# working.net
KiCad netlist of a schematic drawn in EAGLE
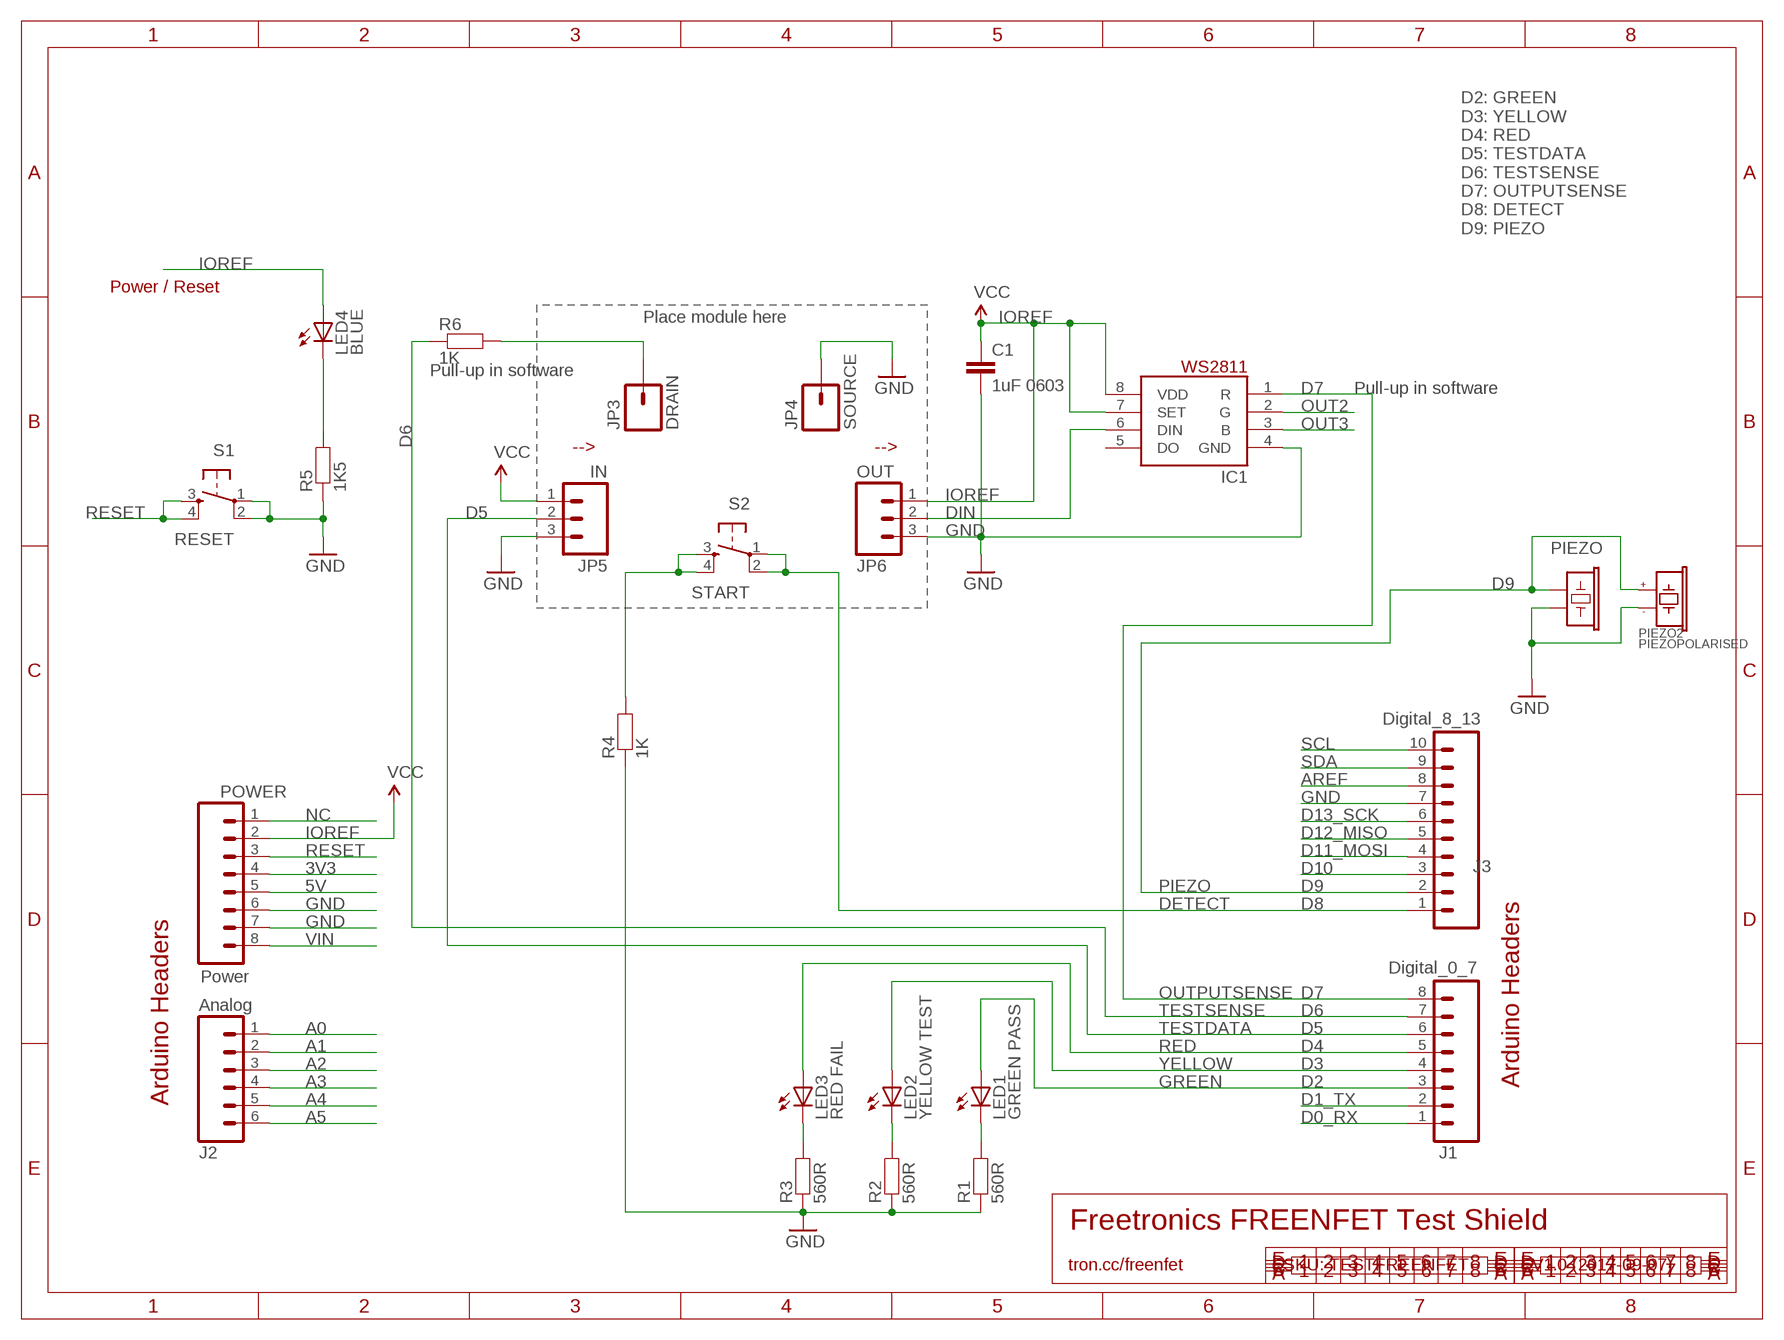
[diagram p0: schematic, sheet 1]

(export (version "E")
  (design (tool "Eeschema 10.0.6"))
  (components
    (comp (ref "C1")
      (value "1uF 0603")
      (footprint "eagle-import:0603")
      (libsource (lib "eagle-import") (part "CAP0603"))
    )
    (comp (ref "IC1")
      (value "WS2811-SOP8")
      (footprint "eagle-import:SO08-SKINNYPADS")
      (libsource (lib "eagle-import") (part "WS2811-SOP8"))
    )
    (comp (ref "J1")
      (value "Digital_0_7")
      (footprint "eagle-import:1X08")
      (libsource (lib "eagle-import") (part "M08"))
    )
    (comp (ref "J2")
      (value "Analog")
      (footprint "eagle-import:1X06")
      (libsource (lib "eagle-import") (part "M06SIP"))
    )
    (comp (ref "J3")
      (value "Digital_8_13")
      (footprint "eagle-import:1X10")
      (libsource (lib "eagle-import") (part "M100.1"))
    )
    (comp (ref "JP3")
      (value "DRAIN")
      (footprint "eagle-import:1X01_2_1_MM")
      (libsource (lib "eagle-import") (part "M012.1MM"))
    )
    (comp (ref "JP4")
      (value "SOURCE")
      (footprint "eagle-import:1X01_2_1_MM")
      (libsource (lib "eagle-import") (part "M012.1MM"))
    )
    (comp (ref "JP5")
      (value "IN")
      (footprint "eagle-import:1X03")
      (libsource (lib "eagle-import") (part "M03PTH"))
    )
    (comp (ref "JP6")
      (value "OUT")
      (footprint "eagle-import:1X03")
      (libsource (lib "eagle-import") (part "M03PTH"))
    )
    (comp (ref "LED1")
      (value "GREEN PASS")
      (footprint "eagle-import:LED-0603")
      (libsource (lib "eagle-import") (part "LED0603"))
    )
    (comp (ref "LED2")
      (value "YELLOW TEST")
      (footprint "eagle-import:LED-0603")
      (libsource (lib "eagle-import") (part "LED0603"))
    )
    (comp (ref "LED3")
      (value "RED FAIL")
      (footprint "eagle-import:LED-0603")
      (libsource (lib "eagle-import") (part "LED0603"))
    )
    (comp (ref "LED4")
      (value "BLUE")
      (footprint "eagle-import:LED-0603")
      (libsource (lib "eagle-import") (part "LED0603"))
    )
    (comp (ref "PIEZO")
      (value "BUZZERSMD12X12")
      (footprint "eagle-import:BUZZER-12X12-SMT")
      (libsource (lib "eagle-import") (part "BUZZERSMD12X12"))
    )
    (comp (ref "PIEZO2")
      (value "PIEZOPOLARISED")
      (footprint "eagle-import:PIEZO12MMWIDEPOLARISED")
      (libsource (lib "eagle-import") (part "PIEZOPOLARISED"))
    )
    (comp (ref "POWER")
      (value "Power")
      (footprint "eagle-import:1X08")
      (libsource (lib "eagle-import") (part "M08"))
    )
    (comp (ref "R1")
      (value "560R")
      (footprint "eagle-import:0603")
      (libsource (lib "eagle-import") (part "RESISTOR0603"))
    )
    (comp (ref "R2")
      (value "560R")
      (footprint "eagle-import:0603")
      (libsource (lib "eagle-import") (part "RESISTOR0603"))
    )
    (comp (ref "R3")
      (value "560R")
      (footprint "eagle-import:0603")
      (libsource (lib "eagle-import") (part "RESISTOR0603"))
    )
    (comp (ref "R4")
      (value "1K")
      (footprint "eagle-import:0603")
      (libsource (lib "eagle-import") (part "RESISTOR0603"))
    )
    (comp (ref "R5")
      (value "1K5")
      (footprint "eagle-import:0603")
      (libsource (lib "eagle-import") (part "RESISTOR0603"))
    )
    (comp (ref "R6")
      (value "1K")
      (footprint "eagle-import:0603")
      (libsource (lib "eagle-import") (part "RESISTOR0603"))
    )
    (comp (ref "S1")
      (value "RESET")
      (footprint "eagle-import:TACTILE-PTH")
      (libsource (lib "eagle-import") (part "TAC_SWITCHPTH"))
    )
    (comp (ref "S2")
      (value "START")
      (footprint "eagle-import:TACTILE-PTH")
      (libsource (lib "eagle-import") (part "TAC_SWITCHPTH"))
    )
  )
  (nets
    (net (code "1") (name "/3V3") (class "Default")
      (node (ref "POWER") (pin "4") (pinfunction "4_4") (pintype "passive"))
    )
    (net (code "2") (name "/5V") (class "Default")
      (node (ref "POWER") (pin "5") (pinfunction "5_5") (pintype "passive"))
    )
    (net (code "3") (name "/A0") (class "Default")
      (node (ref "J2") (pin "1") (pinfunction "1_1") (pintype "passive"))
    )
    (net (code "4") (name "/A1") (class "Default")
      (node (ref "J2") (pin "2") (pinfunction "2_2") (pintype "passive"))
    )
    (net (code "5") (name "/A2") (class "Default")
      (node (ref "J2") (pin "3") (pinfunction "3_3") (pintype "passive"))
    )
    (net (code "6") (name "/A3") (class "Default")
      (node (ref "J2") (pin "4") (pinfunction "4_4") (pintype "passive"))
    )
    (net (code "7") (name "/A4") (class "Default")
      (node (ref "J2") (pin "5") (pinfunction "5_5") (pintype "passive"))
    )
    (net (code "8") (name "/A5") (class "Default")
      (node (ref "J2") (pin "6") (pinfunction "6_6") (pintype "passive"))
    )
    (net (code "9") (name "/AREF") (class "Default")
      (node (ref "J3") (pin "8") (pinfunction "8_8") (pintype "passive"))
    )
    (net (code "10") (name "/D0_RX") (class "Default")
      (node (ref "J1") (pin "1") (pinfunction "1_1") (pintype "passive"))
    )
    (net (code "11") (name "/D1_TX") (class "Default")
      (node (ref "J1") (pin "2") (pinfunction "2_2") (pintype "passive"))
    )
    (net (code "12") (name "/D2") (class "Default")
      (node (ref "J1") (pin "3") (pinfunction "3_3") (pintype "passive"))
      (node (ref "LED1") (pin "A") (pinfunction "A_A") (pintype "passive"))
    )
    (net (code "13") (name "/D3") (class "Default")
      (node (ref "J1") (pin "4") (pinfunction "4_4") (pintype "passive"))
      (node (ref "LED2") (pin "A") (pinfunction "A_A") (pintype "passive"))
    )
    (net (code "14") (name "/D4") (class "Default")
      (node (ref "J1") (pin "5") (pinfunction "5_5") (pintype "passive"))
      (node (ref "LED3") (pin "A") (pinfunction "A_A") (pintype "passive"))
    )
    (net (code "15") (name "/D5") (class "Default")
      (node (ref "J1") (pin "6") (pinfunction "6_6") (pintype "passive"))
      (node (ref "JP5") (pin "2") (pinfunction "2_2") (pintype "passive"))
    )
    (net (code "16") (name "/D6") (class "Default")
      (node (ref "J1") (pin "7") (pinfunction "7_7") (pintype "passive"))
      (node (ref "R6") (pin "1") (pinfunction "1_1") (pintype "passive"))
    )
    (net (code "17") (name "/D7") (class "Default")
      (node (ref "IC1") (pin "1") (pinfunction "R_1") (pintype "open_collector"))
      (node (ref "J1") (pin "8") (pinfunction "8_8") (pintype "passive"))
    )
    (net (code "18") (name "/D8") (class "Default")
      (node (ref "J3") (pin "1") (pinfunction "1_1") (pintype "passive"))
      (node (ref "S2") (pin "1") (pinfunction "1_1") (pintype "passive"))
      (node (ref "S2") (pin "2") (pinfunction "2_2") (pintype "passive"))
    )
    (net (code "19") (name "/D9") (class "Default")
      (node (ref "J3") (pin "2") (pinfunction "2_2") (pintype "passive"))
      (node (ref "PIEZO") (pin "2") (pinfunction "2_2") (pintype "passive"))
      (node (ref "PIEZO2") (pin "1") (pinfunction "+_1") (pintype "bidirectional"))
    )
    (net (code "20") (name "/D10") (class "Default")
      (node (ref "J3") (pin "3") (pinfunction "3_3") (pintype "passive"))
    )
    (net (code "21") (name "/D11_MOSI") (class "Default")
      (node (ref "J3") (pin "4") (pinfunction "4_4") (pintype "passive"))
    )
    (net (code "22") (name "/D12_MISO") (class "Default")
      (node (ref "J3") (pin "5") (pinfunction "5_5") (pintype "passive"))
    )
    (net (code "23") (name "/D13_SCK") (class "Default")
      (node (ref "J3") (pin "6") (pinfunction "6_6") (pintype "passive"))
    )
    (net (code "24") (name "/DIN") (class "Default")
      (node (ref "IC1") (pin "6") (pinfunction "DIN_6") (pintype "input"))
      (node (ref "JP6") (pin "2") (pinfunction "2_2") (pintype "passive"))
    )
    (net (code "25") (name "/NC") (class "Default")
      (node (ref "POWER") (pin "1") (pinfunction "1_1") (pintype "passive"))
    )
    (net (code "26") (name "/OUT2") (class "Default")
      (node (ref "IC1") (pin "2") (pinfunction "G_2") (pintype "open_collector"))
    )
    (net (code "27") (name "/OUT3") (class "Default")
      (node (ref "IC1") (pin "3") (pinfunction "B_3") (pintype "open_collector"))
    )
    (net (code "28") (name "/RESET") (class "Default")
      (node (ref "POWER") (pin "3") (pinfunction "3_3") (pintype "passive"))
      (node (ref "S1") (pin "3") (pinfunction "3_3") (pintype "passive"))
      (node (ref "S1") (pin "4") (pinfunction "4_4") (pintype "passive"))
    )
    (net (code "29") (name "/SCL") (class "Default")
      (node (ref "J3") (pin "10") (pinfunction "10_10") (pintype "passive"))
    )
    (net (code "30") (name "/SDA") (class "Default")
      (node (ref "J3") (pin "9") (pinfunction "9_9") (pintype "passive"))
    )
    (net (code "31") (name "/VIN") (class "Default")
      (node (ref "POWER") (pin "8") (pinfunction "8_8") (pintype "passive"))
    )
    (net (code "32") (name "GND") (class "Default")
      (node (ref "C1") (pin "2") (pinfunction "2_2") (pintype "passive"))
      (node (ref "IC1") (pin "4") (pinfunction "GND_4") (pintype "power_in"))
      (node (ref "J3") (pin "7") (pinfunction "7_7") (pintype "passive"))
      (node (ref "JP4") (pin "1") (pinfunction "1_1") (pintype "passive"))
      (node (ref "JP5") (pin "3") (pinfunction "3_3") (pintype "passive"))
      (node (ref "JP6") (pin "3") (pinfunction "3_3") (pintype "passive"))
      (node (ref "PIEZO") (pin "1") (pinfunction "1_1") (pintype "passive"))
      (node (ref "PIEZO2") (pin "2") (pinfunction "-_2") (pintype "bidirectional"))
      (node (ref "POWER") (pin "6") (pinfunction "6_6") (pintype "passive"))
      (node (ref "POWER") (pin "7") (pinfunction "7_7") (pintype "passive"))
      (node (ref "R1") (pin "1") (pinfunction "1_1") (pintype "passive"))
      (node (ref "R2") (pin "1") (pinfunction "1_1") (pintype "passive"))
      (node (ref "R3") (pin "1") (pinfunction "1_1") (pintype "passive"))
      (node (ref "R4") (pin "1") (pinfunction "1_1") (pintype "passive"))
      (node (ref "R5") (pin "1") (pinfunction "1_1") (pintype "passive"))
      (node (ref "S1") (pin "1") (pinfunction "1_1") (pintype "passive"))
      (node (ref "S1") (pin "2") (pinfunction "2_2") (pintype "passive"))
    )
    (net (code "33") (name "Net-(JP3-Pad1)") (class "Default")
      (node (ref "JP3") (pin "1") (pinfunction "1_1") (pintype "passive"))
      (node (ref "R6") (pin "2") (pinfunction "2_2") (pintype "passive"))
    )
    (net (code "34") (name "Net-(LED1-PadC)") (class "Default")
      (node (ref "LED1") (pin "C") (pinfunction "C_C") (pintype "passive"))
      (node (ref "R1") (pin "2") (pinfunction "2_2") (pintype "passive"))
    )
    (net (code "35") (name "Net-(LED2-PadC)") (class "Default")
      (node (ref "LED2") (pin "C") (pinfunction "C_C") (pintype "passive"))
      (node (ref "R2") (pin "2") (pinfunction "2_2") (pintype "passive"))
    )
    (net (code "36") (name "Net-(LED3-PadC)") (class "Default")
      (node (ref "LED3") (pin "C") (pinfunction "C_C") (pintype "passive"))
      (node (ref "R3") (pin "2") (pinfunction "2_2") (pintype "passive"))
    )
    (net (code "37") (name "Net-(LED4-PadC)") (class "Default")
      (node (ref "LED4") (pin "C") (pinfunction "C_C") (pintype "passive"))
      (node (ref "R5") (pin "2") (pinfunction "2_2") (pintype "passive"))
    )
    (net (code "38") (name "Net-(R4-Pad2)") (class "Default")
      (node (ref "R4") (pin "2") (pinfunction "2_2") (pintype "passive"))
      (node (ref "S2") (pin "3") (pinfunction "3_3") (pintype "passive"))
      (node (ref "S2") (pin "4") (pinfunction "4_4") (pintype "passive"))
    )
    (net (code "39") (name "VCC") (class "Default")
      (node (ref "C1") (pin "1") (pinfunction "1_1") (pintype "passive"))
      (node (ref "IC1") (pin "7") (pinfunction "SET_7") (pintype "input"))
      (node (ref "IC1") (pin "8") (pinfunction "VDD_8") (pintype "power_in"))
      (node (ref "JP5") (pin "1") (pinfunction "1_1") (pintype "passive"))
      (node (ref "JP6") (pin "1") (pinfunction "1_1") (pintype "passive"))
      (node (ref "LED4") (pin "A") (pinfunction "A_A") (pintype "passive"))
      (node (ref "POWER") (pin "2") (pinfunction "2_2") (pintype "passive"))
    )
    (net (code "40") (name "unconnected-(IC1-DO-Pad5)") (class "Default")
      (node (ref "IC1") (pin "5") (pinfunction "DO_5") (pintype "output"))
    )
  )
)
